# buck_boost.net
KiCad netlist of a schematic drawn in Altium Designer
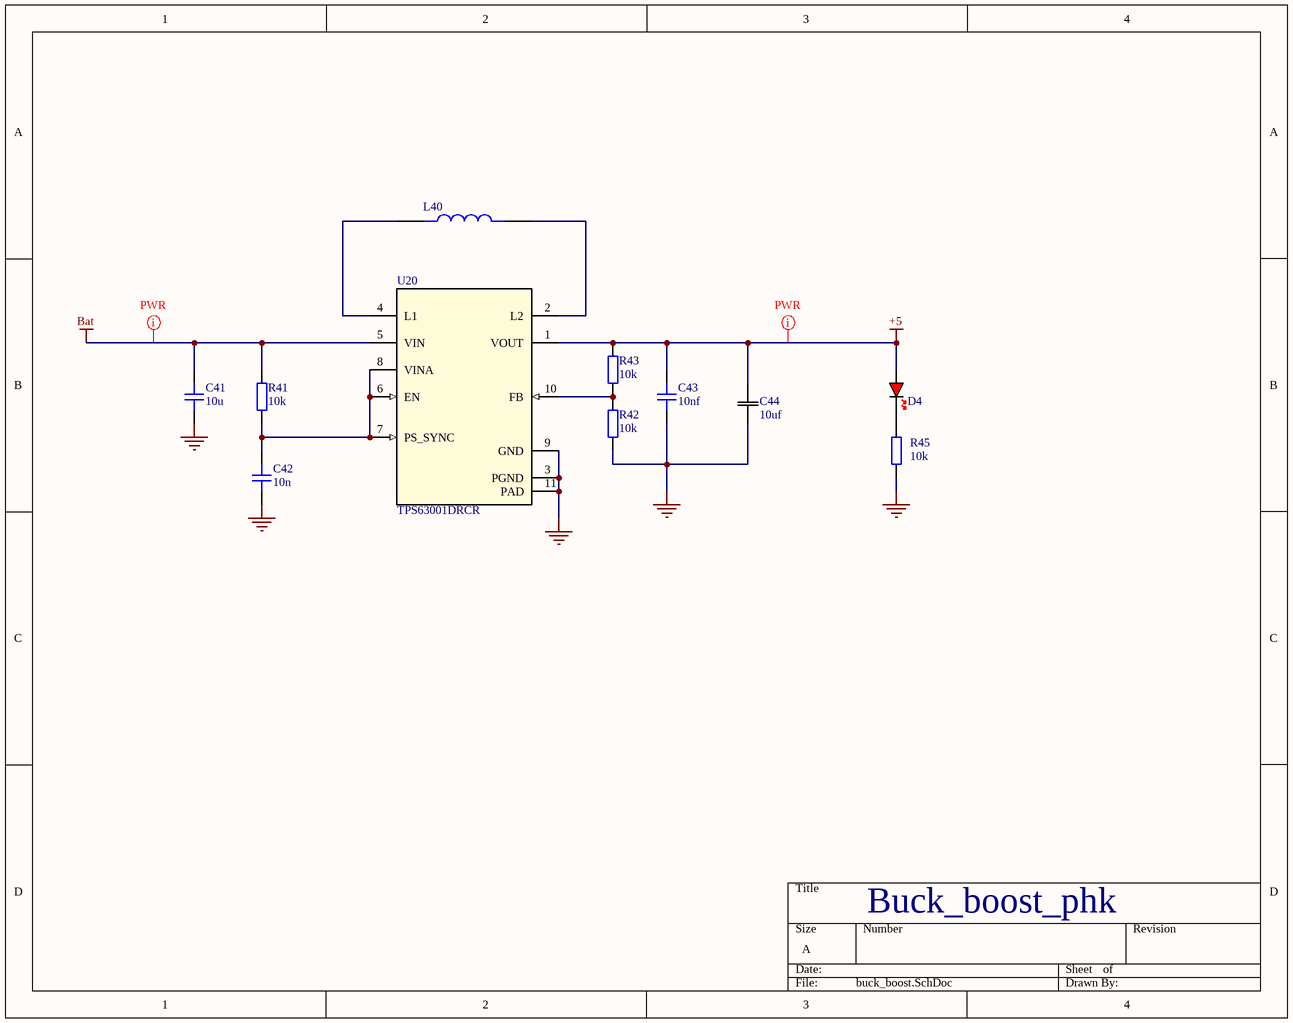
[diagram p0: buck_boost.SchDoc]

(export (version "E")
  (design (tool "Eeschema 10.0.6"))
  (components
    (comp (ref "C41")
      (value "10u")
      (footprint "CAP_0603")
      (description "Capacitor SMD 0603")
      (libsource (lib "Schematic-Lib-PhilsLab") (part "CAP_0603"))
    )
    (comp (ref "C42")
      (value "10n")
      (footprint "CAP_0402")
      (description "Capacitor SMD 0402")
      (libsource (lib "Schematic-Lib-PhilsLab") (part "CAP_0402"))
    )
    (comp (ref "C43")
      (value "10nf")
      (footprint "CAP_0603")
      (description "Capacitor SMD 0603")
      (libsource (lib "Schematic-Lib-PhilsLab") (part "CAP_0603"))
    )
    (comp (ref "C44")
      (value "10uf")
      (footprint "CAP_FN_B_PAN")
      (description "No Description Available")
      (fields
        (field (name "MANUFACTURER_PART_NUMBER") "EEE-FN0J100R")
        (field (name "COPYRIGHT") "Copyright (C) 2026 Ultra Librarian. All rights reserved.")
      )
      (libsource (lib "EEE-FN0J100R") (part "EEE-FN0J100R"))
    )
    (comp (ref "D4")
      (value "RED")
      (footprint "LED_0402_RED")
      (description "LED 0402 RED SMD")
      (libsource (lib "Schematic-Lib-PhilsLab") (part "LED_0402_RED"))
    )
    (comp (ref "L40")
      (value "VLS3012ET-2R2M")
      (footprint "IND_VLS3012ET-2R2M")
      (description "2.2 ÂµH Shielded Drum Core, Wirewound Inductor 1.35 A 96mOhm Max Nonstandard")
      (fields (field (name "MF") "TDK") (field (name "DIGI-KEY_PART_NUMBER") "445-6664-2-ND"))
      (libsource (lib "VLS3012ET-2R2M") (part "VLS3012ET-2R2M"))
    )
    (comp (ref "R41")
      (value "10k")
      (footprint "RES_0402")
      (description "Resistor SMD 0402")
      (libsource (lib "Schematic-Lib-PhilsLab") (part "RES_0402"))
    )
    (comp (ref "R42")
      (value "10k")
      (footprint "RES_0402")
      (description "Resistor SMD 0402")
      (libsource (lib "Schematic-Lib-PhilsLab") (part "RES_0402"))
    )
    (comp (ref "R43")
      (value "10k")
      (footprint "RES_0402")
      (description "Resistor SMD 0402")
      (libsource (lib "Schematic-Lib-PhilsLab") (part "RES_0402"))
    )
    (comp (ref "R45")
      (value "10k")
      (footprint "RES_0402")
      (description "Resistor SMD 0402")
      (libsource (lib "Schematic-Lib-PhilsLab") (part "RES_0402"))
    )
    (comp (ref "U20")
      (value "TPS63001DRCR")
      (footprint "DRC0010J")
      (fields
        (field (name "ALTERNATE_PARTNUMBER") "TPS63001DRCT")
        (field (name "MANUFACTURER") "Texas Instruments")
        (field (name "COPYRIGHT") "Copyright (C) 2025 Ultra Librarian. All rights reserved.")
      )
      (libsource (lib "TPS63001DRCR") (part "TPS63001DRCR"))
    )
  )
  (nets
    (net (code "1") (name "+5") (class "Default")
      (node (ref "C43") (pin "2") (pinfunction "2_2") (pintype "passive"))
      (node (ref "C44") (pin "2") (pinfunction "2_2") (pintype "passive"))
      (node (ref "D4") (pin "A") (pinfunction "A_A") (pintype "passive"))
      (node (ref "R43") (pin "2") (pinfunction "2_2") (pintype "passive"))
      (node (ref "U20") (pin "1") (pinfunction "VOUT_1") (pintype "power_in"))
    )
    (net (code "2") (name "Bat") (class "Default")
      (node (ref "C41") (pin "2") (pinfunction "2_2") (pintype "passive"))
      (node (ref "R41") (pin "2") (pinfunction "2_2") (pintype "passive"))
      (node (ref "U20") (pin "5") (pinfunction "VIN_5") (pintype "power_in"))
    )
    (net (code "3") (name "GND") (class "Default")
      (node (ref "C41") (pin "1") (pinfunction "1_1") (pintype "passive"))
      (node (ref "C42") (pin "1") (pinfunction "1_1") (pintype "passive"))
      (node (ref "C43") (pin "1") (pinfunction "1_1") (pintype "passive"))
      (node (ref "C44") (pin "1") (pinfunction "1_1") (pintype "passive"))
      (node (ref "R42") (pin "1") (pinfunction "1_1") (pintype "passive"))
      (node (ref "R45") (pin "1") (pinfunction "1_1") (pintype "passive"))
      (node (ref "U20") (pin "11") (pinfunction "PAD_11") (pintype "power_in"))
      (node (ref "U20") (pin "3") (pinfunction "PGND_3") (pintype "power_in"))
      (node (ref "U20") (pin "9") (pinfunction "GND_9") (pintype "power_in"))
    )
    (net (code "4") (name "Net-(D4-PadK)") (class "Default")
      (node (ref "D4") (pin "K") (pinfunction "K_K") (pintype "passive"))
      (node (ref "R45") (pin "2") (pinfunction "2_2") (pintype "passive"))
    )
    (net (code "5") (name "Net-(U20-EN)") (class "Default")
      (node (ref "C42") (pin "2") (pinfunction "2_2") (pintype "passive"))
      (node (ref "R41") (pin "1") (pinfunction "1_1") (pintype "passive"))
      (node (ref "U20") (pin "6") (pinfunction "EN_6") (pintype "input"))
      (node (ref "U20") (pin "7") (pinfunction "PS_SYNC_7") (pintype "input"))
      (node (ref "U20") (pin "8") (pinfunction "VINA_8") (pintype "power_in"))
    )
    (net (code "6") (name "Net-(U20-FB)") (class "Default")
      (node (ref "R42") (pin "2") (pinfunction "2_2") (pintype "passive"))
      (node (ref "R43") (pin "1") (pinfunction "1_1") (pintype "passive"))
      (node (ref "U20") (pin "10") (pinfunction "FB_10") (pintype "input"))
    )
    (net (code "7") (name "Net-(U20-L1)") (class "Default")
      (node (ref "L40") (pin "1") (pinfunction "1_1") (pintype "passive"))
      (node (ref "U20") (pin "4") (pinfunction "L1_4") (pintype "passive"))
    )
    (net (code "8") (name "Net-(U20-L2)") (class "Default")
      (node (ref "L40") (pin "2") (pinfunction "2_2") (pintype "passive"))
      (node (ref "U20") (pin "2") (pinfunction "L2_2") (pintype "passive"))
    )
  )
)
